# Temp_datalogger.net
KiCad netlist of a schematic drawn in Altium Designer
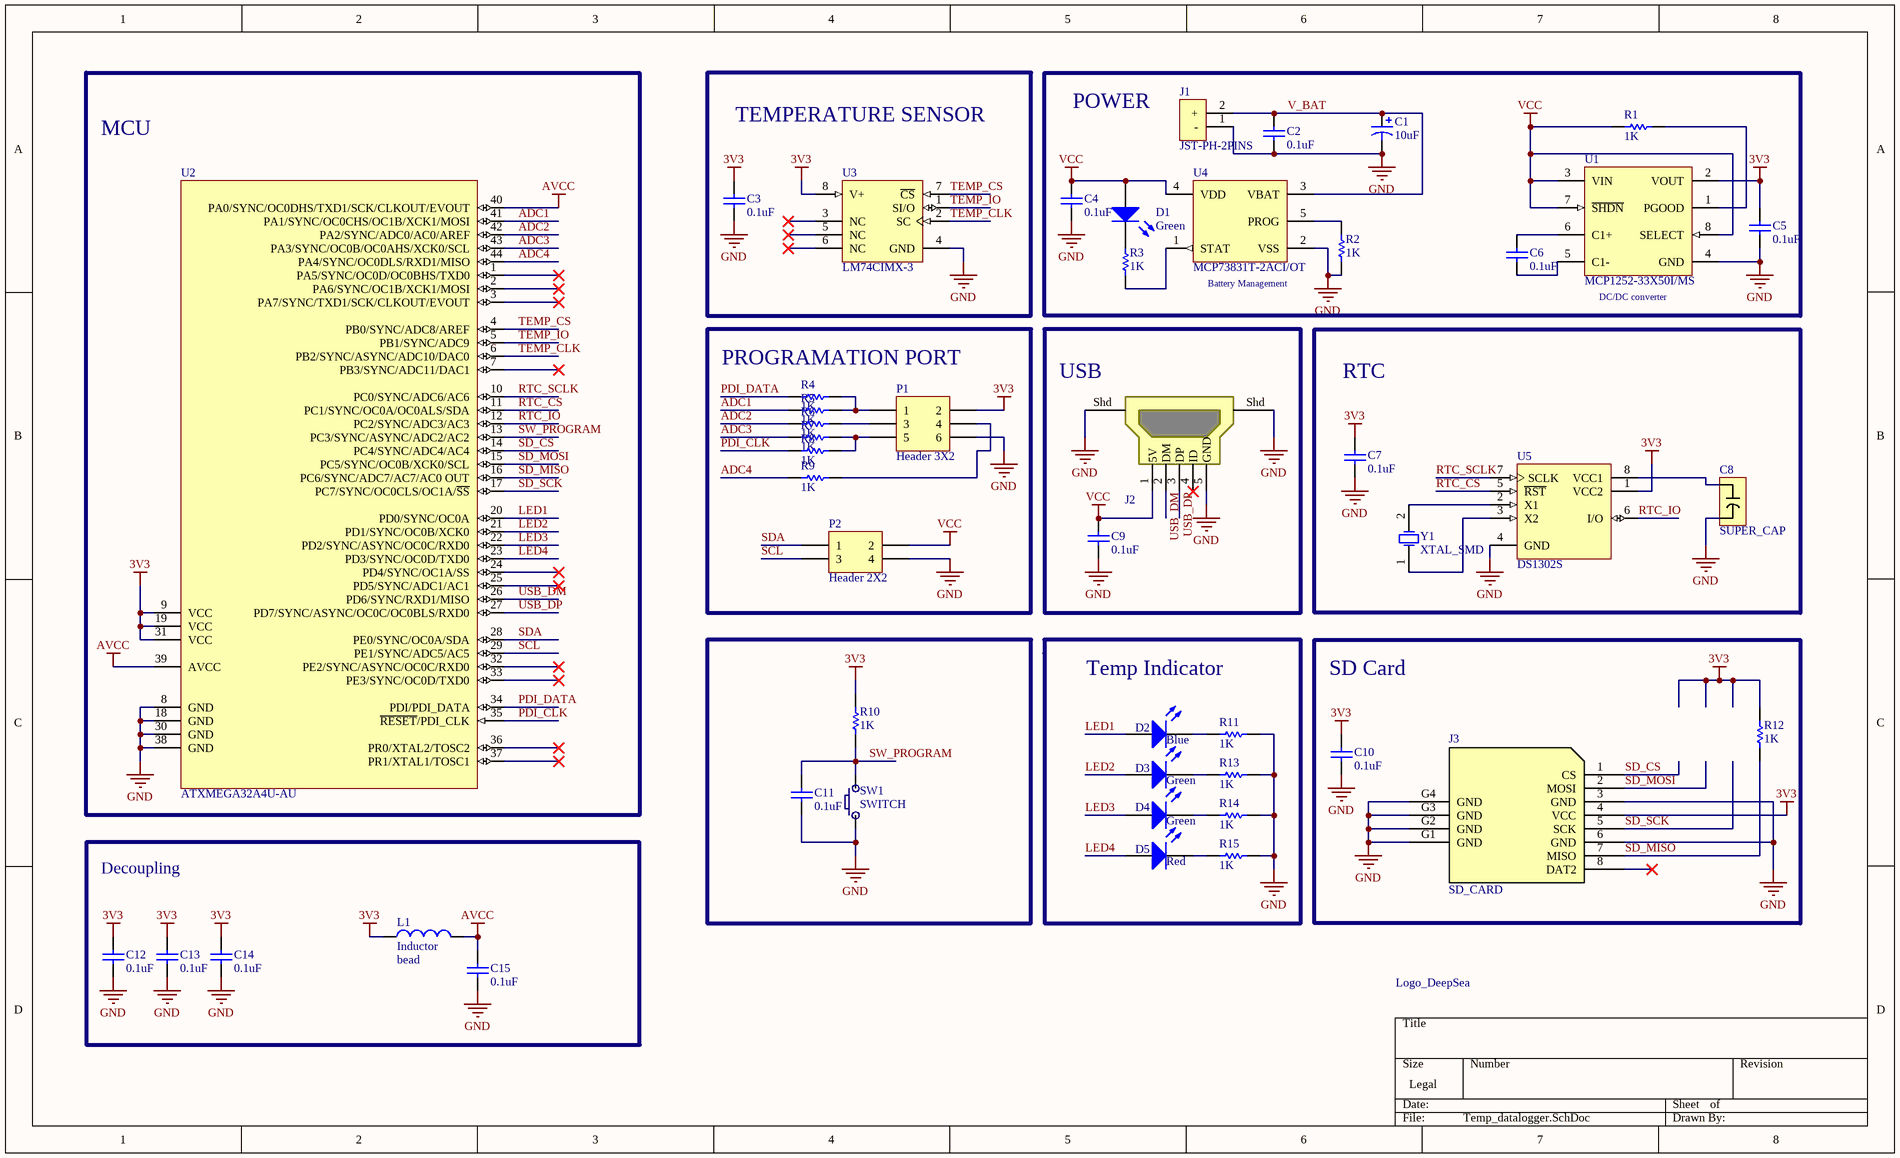
[diagram p0: Temp_datalogger.SchDoc]

(export (version "E")
  (design (tool "Eeschema 10.0.6"))
  (components
    (comp (ref "*")
      (value "Logo_DeepSea")
      (footprint "DeepSea_logo1")
      (libsource (lib "General") (part "Logo_DeepSea"))
    )
    (comp (ref "C1") (value "10uF") (footprint "C_TANT_A_3216_N") (libsource (lib "General") (part "CP_SMD")))
    (comp (ref "C2") (value "0.1uF") (footprint "C0603_N") (libsource (lib "General") (part "C_SMD")))
    (comp (ref "C3") (value "0.1uF") (footprint "C0603_N") (libsource (lib "General") (part "C_SMD")))
    (comp (ref "C4") (value "0.1uF") (footprint "C0603_N") (libsource (lib "General") (part "C_SMD")))
    (comp (ref "C5") (value "0.1uF") (footprint "C0603_N") (libsource (lib "General") (part "C_SMD")))
    (comp (ref "C6") (value "0.1uF") (footprint "C0603_N") (libsource (lib "General") (part "C_SMD")))
    (comp (ref "C7") (value "0.1uF") (footprint "C0603_N") (libsource (lib "General") (part "C_SMD")))
    (comp (ref "C8")
      (value "SUPER_CAP")
      (footprint "414-VA5R")
      (description "CAP SUPER 0.06F 3.3V COIN SMD")
      (fields
        (field (name "MANUFACTURER") "Taiyo Yuden")
        (field (name "MANUFACTURER PART NUMBER") "PAS414HR-VA5R")
      )
      (libsource (lib "General") (part "SUPER_CAP"))
    )
    (comp (ref "C9") (value "0.1uF") (footprint "C0603_N") (libsource (lib "General") (part "C_SMD")))
    (comp (ref "C10") (value "0.1uF") (footprint "C0603_N") (libsource (lib "General") (part "C_SMD")))
    (comp (ref "C11") (value "0.1uF") (footprint "C0603_N") (libsource (lib "General") (part "C_SMD")))
    (comp (ref "C12") (value "0.1uF") (footprint "C0603_N") (libsource (lib "General") (part "C_SMD")))
    (comp (ref "C13") (value "0.1uF") (footprint "C0603_N") (libsource (lib "General") (part "C_SMD")))
    (comp (ref "C14") (value "0.1uF") (footprint "C0603_N") (libsource (lib "General") (part "C_SMD")))
    (comp (ref "C15") (value "0.1uF") (footprint "C0603_N") (libsource (lib "General") (part "C_SMD")))
    (comp (ref "D1")
      (value "Green")
      (footprint "R0603_N")
      (fields (field (name "COLOR") "Green"))
      (libsource (lib "discrete") (part "LED_SMD"))
    )
    (comp (ref "D2")
      (value "Blue")
      (footprint "R0603_N")
      (fields (field (name "COLOR") "Blue"))
      (libsource (lib "discrete") (part "LED_SMD"))
    )
    (comp (ref "D3")
      (value "Green")
      (footprint "R0603_N")
      (fields (field (name "COLOR") "Green"))
      (libsource (lib "discrete") (part "LED_SMD"))
    )
    (comp (ref "D4")
      (value "Green")
      (footprint "R0603_N")
      (fields (field (name "COLOR") "Green"))
      (libsource (lib "discrete") (part "LED_SMD"))
    )
    (comp (ref "D5")
      (value "Red")
      (footprint "R0603_N")
      (fields (field (name "COLOR") "Red"))
      (libsource (lib "discrete") (part "LED_SMD"))
    )
    (comp (ref "J1")
      (value "JST-PH-2PINS")
      (footprint "JST-PH-2")
      (description "CONN HEADER PH SIDE 2POS 2MM SMD")
      (fields
        (field (name "MANUFACTURER") "JST Sales America Inc")
        (field (name "MANUFACTURER PART NUMBER") "S2B-PH-SM4-TB(LF)(SN)")
      )
      (libsource (lib "General") (part "JST-PH-2PINS"))
    )
    (comp (ref "J2")
      (value "MINI_USB")
      (footprint "USB MINI")
      (description "CONN RCPT USB MINI B R/A SMD")
      (fields
        (field (name "MANUFACTURER") "Hirose Electric Co Ltd")
        (field (name "MANUFACTURER PART NUMBER") "UX60SC-MB-5ST(80)")
      )
      (libsource (lib "General") (part "MINI_USB"))
    )
    (comp (ref "J3")
      (value "SD_CARD")
      (footprint "MICRO_SD-SOCKET")
      (description "CONN MEMORY CARD R/A 8POS SMD")
      (fields
        (field (name "MANUFACTURER") "Molex Inc")
        (field (name "MANUFACTURER PART NUMBER") "0472192001")
      )
      (libsource (lib "General") (part "SD_CARD"))
    )
    (comp (ref "L1")
      (value "Inductor")
      (footprint "R0603_N")
      (fields (field (name "ALTIUM_VALUE") "bead") (field (name "PUBLISHER") "Altium Limited"))
      (libsource (lib "Miscellaneous Devices") (part "Inductor"))
    )
    (comp (ref "P1")
      (value "Header 3X2")
      (footprint "HDR2X3")
      (description "Header, 3-Pin, Dual row")
      (fields (field (name "PUBLISHER") "Altium Limited"))
      (libsource (lib "Miscellaneous Connectors") (part "Header 3X2"))
    )
    (comp (ref "P2")
      (value "Header 2X2")
      (footprint "HDR2X2")
      (description "Header, 2-Pin, Dual row")
      (fields (field (name "PUBLISHER") "Altium Limited"))
      (libsource (lib "Miscellaneous Connectors") (part "Header 2X2"))
    )
    (comp (ref "R1") (value "1K") (footprint "R0603_N") (libsource (lib "discrete") (part "R_SMD")))
    (comp (ref "R2") (value "1K") (footprint "R0603_N") (libsource (lib "discrete") (part "R_SMD")))
    (comp (ref "R3") (value "1K") (footprint "R0603_N") (libsource (lib "discrete") (part "R_SMD")))
    (comp (ref "R4") (value "1K") (footprint "R0603_N") (libsource (lib "discrete") (part "R_SMD")))
    (comp (ref "R5") (value "1K") (footprint "R0603_N") (libsource (lib "discrete") (part "R_SMD")))
    (comp (ref "R6") (value "1K") (footprint "R0603_N") (libsource (lib "discrete") (part "R_SMD")))
    (comp (ref "R7") (value "1K") (footprint "R0603_N") (libsource (lib "discrete") (part "R_SMD")))
    (comp (ref "R8") (value "1K") (footprint "R0603_N") (libsource (lib "discrete") (part "R_SMD")))
    (comp (ref "R9") (value "1K") (footprint "R0603_N") (libsource (lib "discrete") (part "R_SMD")))
    (comp (ref "R10") (value "1K") (footprint "R0603_N") (libsource (lib "discrete") (part "R_SMD")))
    (comp (ref "R11") (value "1K") (footprint "R0603_N") (libsource (lib "discrete") (part "R_SMD")))
    (comp (ref "R12") (value "1K") (footprint "R0603_N") (libsource (lib "discrete") (part "R_SMD")))
    (comp (ref "R13") (value "1K") (footprint "R0603_N") (libsource (lib "discrete") (part "R_SMD")))
    (comp (ref "R14") (value "1K") (footprint "R0603_N") (libsource (lib "discrete") (part "R_SMD")))
    (comp (ref "R15") (value "1K") (footprint "R0603_N") (libsource (lib "discrete") (part "R_SMD")))
    (comp (ref "SW1")
      (value "SWITCH")
      (footprint "swich_foot")
      (description "SWITCH TACTILE SPST-NO 0.05A 12V")
      (fields
        (field (name "MANUFACTURER") "TE Connectivity")
        (field (name "MANUFACTURER PART NUMBER") "FSM4JSMATR")
      )
      (libsource (lib "General") (part "SWITCH"))
    )
    (comp (ref "U1")
      (value "MCP1252-33X50I/MS")
      (footprint "MSOP-MS8_L")
      (description "IC REG MULTI CONFIG 0.12A 8MSOP")
      (fields (field (name "MANUFACTURER") "Microchip Technology"))
      (libsource (lib "General") (part "MCP1252-33X50I/MS"))
    )
    (comp (ref "U2")
      (value "ATXMEGA32A4U-AU")
      (footprint "44A_M")
      (description "IC MCU 8BIT 32KB FLASH 44TQFP")
      (fields (field (name "MANUFACTURER") "Atmel"))
      (libsource (lib "General") (part "ATXMEGA32A4U-AU"))
    )
    (comp (ref "U3")
      (value "LM74CIMX-3")
      (footprint "M08A_N")
      (description "SPI/MICROWIRE 12-Bit Plus Sign Temperature Sensor, 8-pin Narrow SOIC")
      (fields
        (field (name "MANUFACTURER") "National Semiconductor")
        (field (name "PUBLISHER") "Altium Limited")
      )
      (libsource (lib "NSC Temperature Sensor") (part "LM74CIMX-3"))
    )
    (comp (ref "U4")
      (value "MCP73831T-2ACI/OT")
      (footprint "SOT-23-OT5_M")
      (description "IC CONTROLLR LI-ION 4.2V SOT23-5")
      (fields (field (name "MANUFACTURER") "Microchip Technology"))
      (libsource (lib "General") (part "MCP73831T-2ACI/OT"))
    )
    (comp (ref "U5")
      (value "DS1302S")
      (footprint "SOIC8WA_N")
      (description "IC TIMEKEEPER T-CHARGE 8-SOIC")
      (fields
        (field (name "MANUFACTURER") "Maxim Integrated")
        (field (name "MANUFACTURER PART NUMBER") "DS1302S+T&R")
      )
      (libsource (lib "General") (part "DS1302S"))
    )
    (comp (ref "Y1")
      (value "XTAL_SMD")
      (footprint "XTAL_SMD-3")
      (libsource (lib "General") (part "XTAL_SMD"))
    )
  )
  (nets
    (net (code "1") (name "/ADC1") (class "Default")
      (node (ref "R5") (pin "1") (pinfunction "1_1") (pintype "passive"))
      (node (ref "U2") (pin "41") (pinfunction "PA1/SYNC/OC0CHS/OC1B/XCK1/MOSI_41") (pintype "bidirectional"))
    )
    (net (code "2") (name "/ADC2") (class "Default")
      (node (ref "R6") (pin "1") (pinfunction "1_1") (pintype "passive"))
      (node (ref "U2") (pin "42") (pinfunction "PA2/SYNC/ADC0/AC0/AREF_42") (pintype "bidirectional"))
    )
    (net (code "3") (name "/ADC3") (class "Default")
      (node (ref "R7") (pin "1") (pinfunction "1_1") (pintype "passive"))
      (node (ref "U2") (pin "43") (pinfunction "PA3/SYNC/OC0B/OC0AHS/XCK0/SCL_43") (pintype "bidirectional"))
    )
    (net (code "4") (name "/ADC4") (class "Default")
      (node (ref "R9") (pin "1") (pinfunction "1_1") (pintype "passive"))
      (node (ref "U2") (pin "44") (pinfunction "PA4/SYNC/OC0DLS/RXD1/MISO_44") (pintype "bidirectional"))
    )
    (net (code "5") (name "/LED1") (class "Default")
      (node (ref "D2") (pin "1") (pinfunction "A_1") (pintype "passive"))
      (node (ref "U2") (pin "20") (pinfunction "PD0/SYNC/OC0A_20") (pintype "bidirectional"))
    )
    (net (code "6") (name "/LED2") (class "Default")
      (node (ref "D3") (pin "1") (pinfunction "A_1") (pintype "passive"))
      (node (ref "U2") (pin "21") (pinfunction "PD1/SYNC/OC0B/XCK0_21") (pintype "bidirectional"))
    )
    (net (code "7") (name "/LED3") (class "Default")
      (node (ref "D4") (pin "1") (pinfunction "A_1") (pintype "passive"))
      (node (ref "U2") (pin "22") (pinfunction "PD2/SYNC/ASYNC/OC0C/RXD0_22") (pintype "bidirectional"))
    )
    (net (code "8") (name "/LED4") (class "Default")
      (node (ref "D5") (pin "1") (pinfunction "A_1") (pintype "passive"))
      (node (ref "U2") (pin "23") (pinfunction "PD3/SYNC/OC0D/TXD0_23") (pintype "bidirectional"))
    )
    (net (code "9") (name "/PDI_CLK") (class "Default")
      (node (ref "R8") (pin "1") (pinfunction "1_1") (pintype "passive"))
      (node (ref "U2") (pin "35") (pinfunction "~{RESET}/PDI_CLK_35") (pintype "input"))
    )
    (net (code "10") (name "/PDI_DATA") (class "Default")
      (node (ref "R4") (pin "1") (pinfunction "1_1") (pintype "passive"))
      (node (ref "U2") (pin "34") (pinfunction "PDI/PDI_DATA_34") (pintype "bidirectional"))
    )
    (net (code "11") (name "/RTC_CS") (class "Default")
      (node (ref "U2") (pin "11") (pinfunction "PC1/SYNC/OC0A/OC0ALS/SDA_11") (pintype "bidirectional"))
      (node (ref "U5") (pin "5") (pinfunction "~{RST}_5") (pintype "input"))
    )
    (net (code "12") (name "/RTC_IO") (class "Default")
      (node (ref "U2") (pin "12") (pinfunction "PC2/SYNC/ADC3/AC3_12") (pintype "bidirectional"))
      (node (ref "U5") (pin "6") (pinfunction "I/O_6") (pintype "bidirectional"))
    )
    (net (code "13") (name "/RTC_SCLK") (class "Default")
      (node (ref "U2") (pin "10") (pinfunction "PC0/SYNC/ADC6/AC6_10") (pintype "bidirectional"))
      (node (ref "U5") (pin "7") (pinfunction "SCLK_7") (pintype "input"))
    )
    (net (code "14") (name "/SCL") (class "Default")
      (node (ref "P2") (pin "3") (pinfunction "3_3") (pintype "passive"))
      (node (ref "U2") (pin "29") (pinfunction "PE1/SYNC/ADC5/AC5_29") (pintype "bidirectional"))
    )
    (net (code "15") (name "/SDA") (class "Default")
      (node (ref "P2") (pin "1") (pinfunction "1_1") (pintype "passive"))
      (node (ref "U2") (pin "28") (pinfunction "PE0/SYNC/OC0A/SDA_28") (pintype "bidirectional"))
    )
    (net (code "16") (name "/SD_CS") (class "Default")
      (node (ref "J3") (pin "1") (pinfunction "CS_1") (pintype "passive"))
      (node (ref "U2") (pin "14") (pinfunction "PC4/SYNC/ADC4/AC4_14") (pintype "bidirectional"))
    )
    (net (code "17") (name "/SD_MISO") (class "Default")
      (node (ref "J3") (pin "7") (pinfunction "MISO_7") (pintype "passive"))
      (node (ref "R12") (pin "1") (pinfunction "1_1") (pintype "passive"))
      (node (ref "U2") (pin "16") (pinfunction "PC6/SYNC/ADC7/AC7/AC0_OUT_16") (pintype "bidirectional"))
    )
    (net (code "18") (name "/SD_MOSI") (class "Default")
      (node (ref "J3") (pin "2") (pinfunction "MOSI_2") (pintype "passive"))
      (node (ref "U2") (pin "15") (pinfunction "PC5/SYNC/OC0B/XCK0/SCL_15") (pintype "bidirectional"))
    )
    (net (code "19") (name "/SD_SCK") (class "Default")
      (node (ref "J3") (pin "5") (pinfunction "SCK_5") (pintype "passive"))
      (node (ref "U2") (pin "17") (pinfunction "PC7/SYNC/OC0CLS/OC1A/~{SS}_17") (pintype "bidirectional"))
    )
    (net (code "20") (name "/SW_PROGRAM") (class "Default")
      (node (ref "C11") (pin "1") (pinfunction "1_1") (pintype "passive"))
      (node (ref "R10") (pin "1") (pinfunction "1_1") (pintype "passive"))
      (node (ref "SW1") (pin "2") (pinfunction "*_2") (pintype "passive"))
      (node (ref "U2") (pin "13") (pinfunction "PC3/SYNC/ASYNC/ADC2/AC2_13") (pintype "bidirectional"))
    )
    (net (code "21") (name "/TEMP_CLK") (class "Default")
      (node (ref "U2") (pin "6") (pinfunction "PB2/SYNC/ASYNC/ADC10/DAC0_6") (pintype "bidirectional"))
      (node (ref "U3") (pin "2") (pinfunction "SC_2") (pintype "input"))
    )
    (net (code "22") (name "/TEMP_CS") (class "Default")
      (node (ref "U2") (pin "4") (pinfunction "PB0/SYNC/ADC8/AREF_4") (pintype "bidirectional"))
      (node (ref "U3") (pin "7") (pinfunction "~{CS}_7") (pintype "input"))
    )
    (net (code "23") (name "/TEMP_IO") (class "Default")
      (node (ref "U2") (pin "5") (pinfunction "PB1/SYNC/ADC9_5") (pintype "bidirectional"))
      (node (ref "U3") (pin "1") (pinfunction "SI/O_1") (pintype "bidirectional"))
    )
    (net (code "24") (name "/USB_DM") (class "Default")
      (node (ref "J2") (pin "2") (pinfunction "DM_2") (pintype "passive"))
      (node (ref "U2") (pin "26") (pinfunction "PD6/SYNC/RXD1/MISO_26") (pintype "bidirectional"))
    )
    (net (code "25") (name "/USB_DP") (class "Default")
      (node (ref "J2") (pin "3") (pinfunction "DP_3") (pintype "passive"))
      (node (ref "U2") (pin "27") (pinfunction "PD7/SYNC/ASYNC/OC0C/OC0BLS/RXD0_27") (pintype "bidirectional"))
    )
    (net (code "26") (name "/V_BAT") (class "Default")
      (node (ref "C1") (pin "1") (pinfunction "1_1") (pintype "passive"))
      (node (ref "C2") (pin "2") (pinfunction "2_2") (pintype "passive"))
      (node (ref "J1") (pin "2") (pinfunction "+_2") (pintype "passive"))
      (node (ref "U4") (pin "3") (pinfunction "VBAT_3") (pintype "power_in"))
    )
    (net (code "27") (name "3V3") (class "Default")
      (node (ref "C10") (pin "1") (pinfunction "1_1") (pintype "passive"))
      (node (ref "C12") (pin "2") (pinfunction "2_2") (pintype "passive"))
      (node (ref "C13") (pin "2") (pinfunction "2_2") (pintype "passive"))
      (node (ref "C14") (pin "2") (pinfunction "2_2") (pintype "passive"))
      (node (ref "C3") (pin "2") (pinfunction "2_2") (pintype "passive"))
      (node (ref "C5") (pin "2") (pinfunction "2_2") (pintype "passive"))
      (node (ref "C7") (pin "2") (pinfunction "2_2") (pintype "passive"))
      (node (ref "J3") (pin "4") (pinfunction "VCC_4") (pintype "passive"))
      (node (ref "L1") (pin "1") (pinfunction "1_1") (pintype "passive"))
      (node (ref "P1") (pin "2") (pinfunction "2_2") (pintype "passive"))
      (node (ref "R10") (pin "2") (pinfunction "2_2") (pintype "passive"))
      (node (ref "R12") (pin "2") (pinfunction "2_2") (pintype "passive"))
      (node (ref "U1") (pin "2") (pinfunction "VOUT_2") (pintype "power_in"))
      (node (ref "U2") (pin "19") (pinfunction "VCC_19") (pintype "power_in"))
      (node (ref "U2") (pin "31") (pinfunction "VCC_31") (pintype "power_in"))
      (node (ref "U2") (pin "9") (pinfunction "VCC_9") (pintype "power_in"))
      (node (ref "U3") (pin "8") (pinfunction "V+_8") (pintype "input"))
      (node (ref "U5") (pin "1") (pinfunction "VCC2_1") (pintype "power_in"))
    )
    (net (code "28") (name "AVCC") (class "Default")
      (node (ref "C15") (pin "2") (pinfunction "2_2") (pintype "passive"))
      (node (ref "L1") (pin "2") (pinfunction "2_2") (pintype "passive"))
      (node (ref "U2") (pin "39") (pinfunction "AVCC_39") (pintype "power_in"))
      (node (ref "U2") (pin "40") (pinfunction "PA0/SYNC/OC0DHS/TXD1/SCK/CLKOUT/EVOUT_40") (pintype "bidirectional"))
    )
    (net (code "29") (name "GND") (class "Default")
      (node (ref "C1") (pin "2") (pinfunction "2_2") (pintype "passive"))
      (node (ref "C10") (pin "2") (pinfunction "2_2") (pintype "passive"))
      (node (ref "C11") (pin "2") (pinfunction "2_2") (pintype "passive"))
      (node (ref "C12") (pin "1") (pinfunction "1_1") (pintype "passive"))
      (node (ref "C13") (pin "1") (pinfunction "1_1") (pintype "passive"))
      (node (ref "C14") (pin "1") (pinfunction "1_1") (pintype "passive"))
      (node (ref "C15") (pin "1") (pinfunction "1_1") (pintype "passive"))
      (node (ref "C2") (pin "1") (pinfunction "1_1") (pintype "passive"))
      (node (ref "C3") (pin "1") (pinfunction "1_1") (pintype "passive"))
      (node (ref "C4") (pin "1") (pinfunction "1_1") (pintype "passive"))
      (node (ref "C5") (pin "1") (pinfunction "1_1") (pintype "passive"))
      (node (ref "C7") (pin "1") (pinfunction "1_1") (pintype "passive"))
      (node (ref "C8") (pin "2") (pinfunction "*_2") (pintype "passive"))
      (node (ref "C9") (pin "1") (pinfunction "1_1") (pintype "passive"))
      (node (ref "J1") (pin "1") (pinfunction "-_1") (pintype "passive"))
      (node (ref "J2") (pin "5") (pinfunction "GND_5") (pintype "power_in"))
      (node (ref "J2") (pin "Shd") (pinfunction "7_Shd") (pintype "passive"))
      (node (ref "J3") (pin "3") (pinfunction "GND_3") (pintype "passive"))
      (node (ref "J3") (pin "6") (pinfunction "GND_6") (pintype "passive"))
      (node (ref "J3") (pin "G1") (pinfunction "GND_G1") (pintype "passive"))
      (node (ref "J3") (pin "G2") (pinfunction "GND_G2") (pintype "passive"))
      (node (ref "J3") (pin "G3") (pinfunction "GND_G3") (pintype "passive"))
      (node (ref "J3") (pin "G4") (pinfunction "GND_G4") (pintype "passive"))
      (node (ref "P1") (pin "6") (pinfunction "6_6") (pintype "passive"))
      (node (ref "P2") (pin "4") (pinfunction "4_4") (pintype "passive"))
      (node (ref "R11") (pin "1") (pinfunction "1_1") (pintype "passive"))
      (node (ref "R13") (pin "1") (pinfunction "1_1") (pintype "passive"))
      (node (ref "R14") (pin "1") (pinfunction "1_1") (pintype "passive"))
      (node (ref "R15") (pin "1") (pinfunction "1_1") (pintype "passive"))
      (node (ref "R2") (pin "1") (pinfunction "1_1") (pintype "passive"))
      (node (ref "SW1") (pin "1") (pinfunction "*_1") (pintype "passive"))
      (node (ref "U1") (pin "4") (pinfunction "GND_4") (pintype "power_in"))
      (node (ref "U2") (pin "18") (pinfunction "GND_18") (pintype "power_in"))
      (node (ref "U2") (pin "30") (pinfunction "GND_30") (pintype "power_in"))
      (node (ref "U2") (pin "38") (pinfunction "GND_38") (pintype "power_in"))
      (node (ref "U2") (pin "8") (pinfunction "GND_8") (pintype "power_in"))
      (node (ref "U3") (pin "4") (pinfunction "GND_4") (pintype "power_in"))
      (node (ref "U4") (pin "2") (pinfunction "VSS_2") (pintype "power_in"))
      (node (ref "U5") (pin "4") (pinfunction "GND_4") (pintype "power_in"))
    )
    (net (code "30") (name "Net-(D1-K)") (class "Default")
      (node (ref "D1") (pin "2") (pinfunction "K_2") (pintype "passive"))
      (node (ref "R3") (pin "1") (pinfunction "1_1") (pintype "passive"))
    )
    (net (code "31") (name "Net-(D2-K)") (class "Default")
      (node (ref "D2") (pin "2") (pinfunction "K_2") (pintype "passive"))
      (node (ref "R11") (pin "2") (pinfunction "2_2") (pintype "passive"))
    )
    (net (code "32") (name "Net-(D3-K)") (class "Default")
      (node (ref "D3") (pin "2") (pinfunction "K_2") (pintype "passive"))
      (node (ref "R13") (pin "2") (pinfunction "2_2") (pintype "passive"))
    )
    (net (code "33") (name "Net-(D4-K)") (class "Default")
      (node (ref "D4") (pin "2") (pinfunction "K_2") (pintype "passive"))
      (node (ref "R14") (pin "2") (pinfunction "2_2") (pintype "passive"))
    )
    (net (code "34") (name "Net-(D5-K)") (class "Default")
      (node (ref "D5") (pin "2") (pinfunction "K_2") (pintype "passive"))
      (node (ref "R15") (pin "2") (pinfunction "2_2") (pintype "passive"))
    )
    (net (code "35") (name "Net-(P1-Pad1)") (class "Default")
      (node (ref "P1") (pin "1") (pinfunction "1_1") (pintype "passive"))
      (node (ref "R4") (pin "2") (pinfunction "2_2") (pintype "passive"))
      (node (ref "R5") (pin "2") (pinfunction "2_2") (pintype "passive"))
    )
    (net (code "36") (name "Net-(P1-Pad3)") (class "Default")
      (node (ref "P1") (pin "3") (pinfunction "3_3") (pintype "passive"))
      (node (ref "R6") (pin "2") (pinfunction "2_2") (pintype "passive"))
    )
    (net (code "37") (name "Net-(P1-Pad4)") (class "Default")
      (node (ref "P1") (pin "4") (pinfunction "4_4") (pintype "passive"))
      (node (ref "R9") (pin "2") (pinfunction "2_2") (pintype "passive"))
    )
    (net (code "38") (name "Net-(P1-Pad5)") (class "Default")
      (node (ref "P1") (pin "5") (pinfunction "5_5") (pintype "passive"))
      (node (ref "R7") (pin "2") (pinfunction "2_2") (pintype "passive"))
      (node (ref "R8") (pin "2") (pinfunction "2_2") (pintype "passive"))
    )
    (net (code "39") (name "Net-(U1-C1+)") (class "Default")
      (node (ref "C6") (pin "2") (pinfunction "2_2") (pintype "passive"))
      (node (ref "U1") (pin "6") (pinfunction "C1+_6") (pintype "passive"))
    )
    (net (code "40") (name "Net-(U1-C1-)") (class "Default")
      (node (ref "C6") (pin "1") (pinfunction "1_1") (pintype "passive"))
      (node (ref "U1") (pin "5") (pinfunction "C1-_5") (pintype "passive"))
    )
    (net (code "41") (name "Net-(U1-PGOOD)") (class "Default")
      (node (ref "R1") (pin "1") (pinfunction "1_1") (pintype "passive"))
      (node (ref "U1") (pin "1") (pinfunction "PGOOD_1") (pintype "open_collector"))
    )
    (net (code "42") (name "Net-(U4-PROG)") (class "Default")
      (node (ref "R2") (pin "2") (pinfunction "2_2") (pintype "passive"))
      (node (ref "U4") (pin "5") (pinfunction "PROG_5") (pintype "passive"))
    )
    (net (code "43") (name "Net-(U4-STAT)") (class "Default")
      (node (ref "R3") (pin "2") (pinfunction "2_2") (pintype "passive"))
      (node (ref "U4") (pin "1") (pinfunction "STAT_1") (pintype "output"))
    )
    (net (code "44") (name "Net-(U5-VCC1)") (class "Default")
      (node (ref "C8") (pin "1") (pinfunction "*_1") (pintype "passive"))
      (node (ref "U5") (pin "8") (pinfunction "VCC1_8") (pintype "power_in"))
    )
    (net (code "45") (name "Net-(U5-X1)") (class "Default")
      (node (ref "U5") (pin "2") (pinfunction "X1_2") (pintype "input"))
      (node (ref "Y1") (pin "2") (pinfunction "OSC2_2") (pintype "passive"))
    )
    (net (code "46") (name "Net-(U5-X2)") (class "Default")
      (node (ref "U5") (pin "3") (pinfunction "X2_3") (pintype "input"))
      (node (ref "Y1") (pin "1") (pinfunction "OSC1_1") (pintype "passive"))
    )
    (net (code "47") (name "VCC") (class "Default")
      (node (ref "C4") (pin "2") (pinfunction "2_2") (pintype "passive"))
      (node (ref "C9") (pin "2") (pinfunction "2_2") (pintype "passive"))
      (node (ref "D1") (pin "1") (pinfunction "A_1") (pintype "passive"))
      (node (ref "J2") (pin "1") (pinfunction "5V_1") (pintype "power_in"))
      (node (ref "P2") (pin "2") (pinfunction "2_2") (pintype "passive"))
      (node (ref "R1") (pin "2") (pinfunction "2_2") (pintype "passive"))
      (node (ref "U1") (pin "3") (pinfunction "VIN_3") (pintype "power_in"))
      (node (ref "U1") (pin "7") (pinfunction "~{SHDN}_7") (pintype "input"))
      (node (ref "U1") (pin "8") (pinfunction "SELECT_8") (pintype "input"))
      (node (ref "U4") (pin "4") (pinfunction "VDD_4") (pintype "power_in"))
    )
    (net (code "48") (name "unconnected-(J2-ID-Pad4)") (class "Default")
      (node (ref "J2") (pin "4") (pinfunction "ID_4") (pintype "passive+no_connect"))
    )
    (net (code "49") (name "unconnected-(J3-DAT2-Pad8)") (class "Default")
      (node (ref "J3") (pin "8") (pinfunction "DAT2_8") (pintype "passive+no_connect"))
    )
    (net (code "50") (name "unconnected-(U2-PA5{slash}SYNC{slash}OC0D{slash}OC0BHS{slash}TXD0-Pad1)") (class "Default")
      (node (ref "U2") (pin "1") (pinfunction "PA5/SYNC/OC0D/OC0BHS/TXD0_1") (pintype "bidirectional+no_connect"))
    )
    (net (code "51") (name "unconnected-(U2-PA6{slash}SYNC{slash}OC1B{slash}XCK1{slash}MOSI-Pad2)") (class "Default")
      (node (ref "U2") (pin "2") (pinfunction "PA6/SYNC/OC1B/XCK1/MOSI_2") (pintype "bidirectional+no_connect"))
    )
    (net (code "52") (name "unconnected-(U2-PA7{slash}SYNC{slash}TXD1{slash}SCK{slash}CLKOUT{slash}EVOUT-Pad3)") (class "Default")
      (node (ref "U2") (pin "3") (pinfunction "PA7/SYNC/TXD1/SCK/CLKOUT/EVOUT_3") (pintype "bidirectional+no_connect"))
    )
    (net (code "53") (name "unconnected-(U2-PB3{slash}SYNC{slash}ADC11{slash}DAC1-Pad7)") (class "Default")
      (node (ref "U2") (pin "7") (pinfunction "PB3/SYNC/ADC11/DAC1_7") (pintype "bidirectional+no_connect"))
    )
    (net (code "54") (name "unconnected-(U2-PD4{slash}SYNC{slash}OC1A{slash}SS-Pad24)") (class "Default")
      (node (ref "U2") (pin "24") (pinfunction "PD4/SYNC/OC1A/SS_24") (pintype "bidirectional+no_connect"))
    )
    (net (code "55") (name "unconnected-(U2-PD5{slash}SYNC{slash}ADC1{slash}AC1-Pad25)") (class "Default")
      (node (ref "U2") (pin "25") (pinfunction "PD5/SYNC/ADC1/AC1_25") (pintype "bidirectional+no_connect"))
    )
    (net (code "56") (name "unconnected-(U2-PE2{slash}SYNC{slash}ASYNC{slash}OC0C{slash}RXD0-Pad32)") (class "Default")
      (node (ref "U2") (pin "32") (pinfunction "PE2/SYNC/ASYNC/OC0C/RXD0_32") (pintype "bidirectional+no_connect"))
    )
    (net (code "57") (name "unconnected-(U2-PE3{slash}SYNC{slash}OC0D{slash}TXD0-Pad33)") (class "Default")
      (node (ref "U2") (pin "33") (pinfunction "PE3/SYNC/OC0D/TXD0_33") (pintype "bidirectional+no_connect"))
    )
    (net (code "58") (name "unconnected-(U2-PR0{slash}XTAL2{slash}TOSC2-Pad36)") (class "Default")
      (node (ref "U2") (pin "36") (pinfunction "PR0/XTAL2/TOSC2_36") (pintype "bidirectional+no_connect"))
    )
    (net (code "59") (name "unconnected-(U2-PR1{slash}XTAL1{slash}TOSC1-Pad37)") (class "Default")
      (node (ref "U2") (pin "37") (pinfunction "PR1/XTAL1/TOSC1_37") (pintype "bidirectional+no_connect"))
    )
    (net (code "60") (name "unconnected-(U3-NC-Pad3)") (class "Default")
      (node (ref "U3") (pin "3") (pinfunction "NC_3") (pintype "passive+no_connect"))
    )
    (net (code "61") (name "unconnected-(U3-NC-Pad5)") (class "Default")
      (node (ref "U3") (pin "5") (pinfunction "NC_5") (pintype "passive+no_connect"))
    )
    (net (code "62") (name "unconnected-(U3-NC-Pad6)") (class "Default")
      (node (ref "U3") (pin "6") (pinfunction "NC_6") (pintype "passive+no_connect"))
    )
  )
)
